# Power.net
KiCad netlist of a schematic drawn in Altium Designer
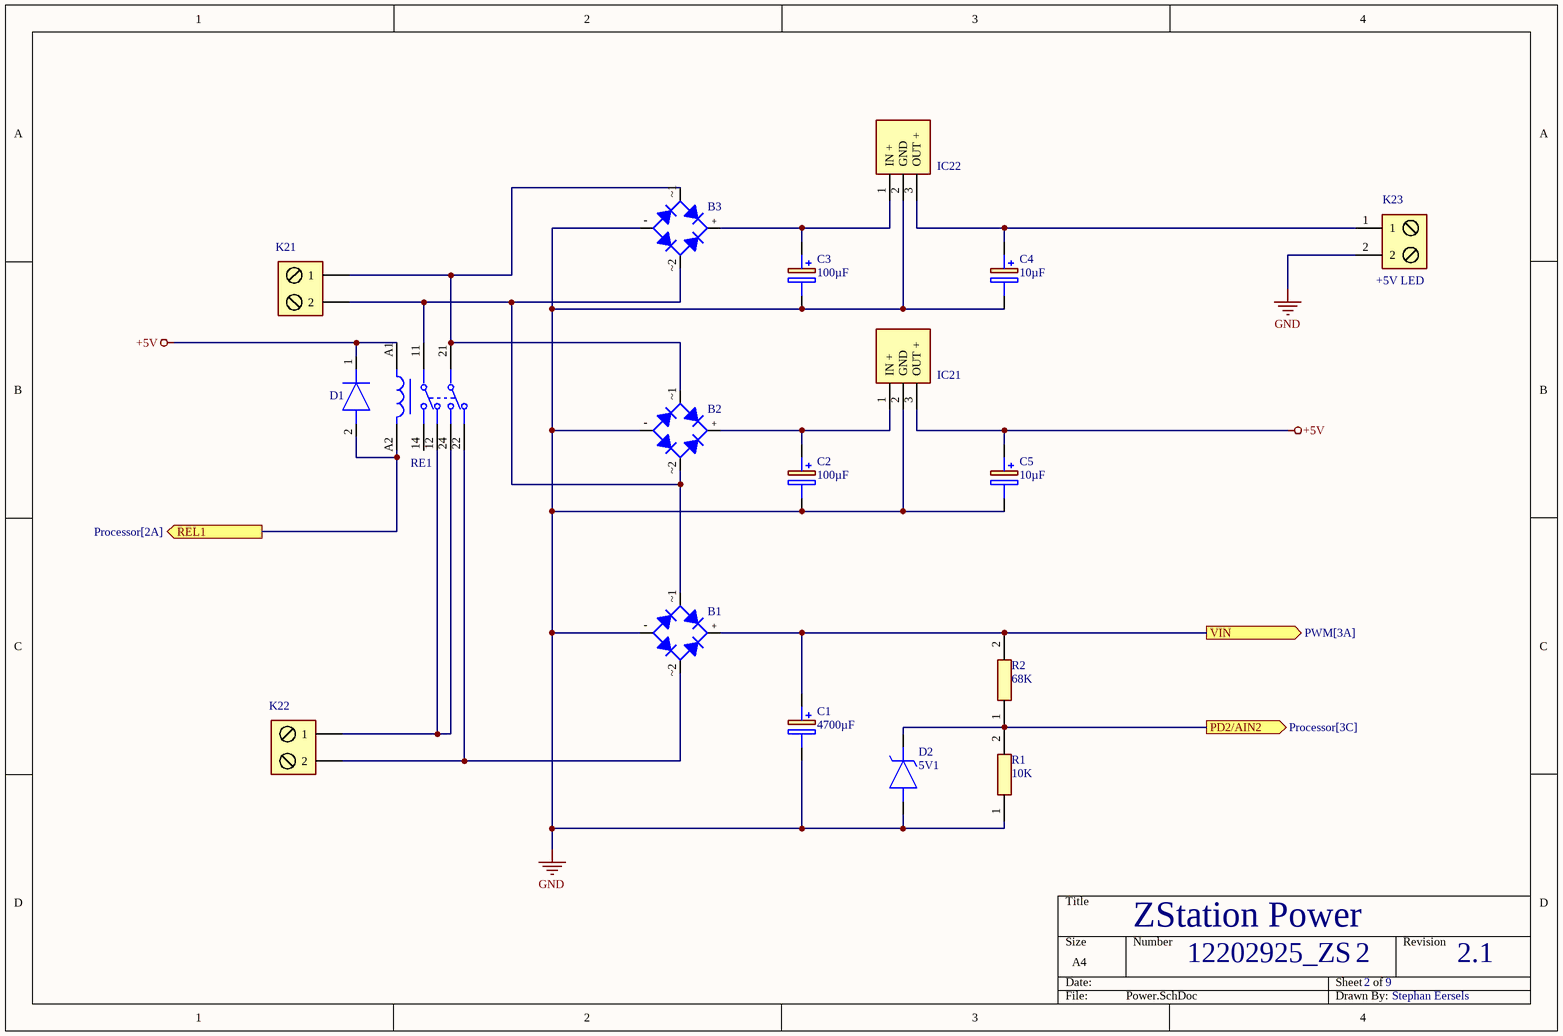
[diagram p0: Power.SchDoc]

(export (version "E")
  (design (tool "Eeschema 10.0.6"))
  (components
    (comp (ref "B1")
      (value "Bridge_Classic")
      (footprint "GBU6JE345")
      (description "Bridge Rectifiers 6.0 Amp 600 Volt")
      (fields (field (name "MANUFACTURER") "Diodes Inc"))
      (libsource (lib "Master") (part "Bridge_Classic"))
    )
    (comp (ref "B2")
      (value "Bridge_Classic")
      (footprint "GBU6JE345")
      (description "Bridge Rectifiers 6.0 Amp 600 Volt")
      (fields (field (name "MANUFACTURER") "Diodes Inc"))
      (libsource (lib "Master") (part "Bridge_Classic"))
    )
    (comp (ref "B3")
      (value "Bridge_Classic")
      (footprint "GBU6JE345")
      (description "Bridge Rectifiers 6.0 Amp 600 Volt")
      (fields (field (name "MANUFACTURER") "Diodes Inc"))
      (libsource (lib "Master") (part "Bridge_Classic"))
    )
    (comp (ref "C1")
      (value "4700µF")
      (footprint "SamacSys:CAPPRD250W52D630H1250")
      (description "Aluminium Electrolytic Capacitors - Radial Leaded WCAP-ATG8 4700uF 50V 20% Radial")
      (fields
        (field (name "MANUFACTURER_PART_NUMBER") "860040473003")
        (field (name "MOUSER PART NUMBER") "710-860040473003")
      )
      (libsource (lib "Master") (part "CAP_4700µF_50V"))
    )
    (comp (ref "C2")
      (value "100µF")
      (footprint "SamacSys:CAPPRD250W52D630H1250")
      (description "Aluminium Electrolytic Capacitors - Radial Leaded WCAP-ATUL 100uF 25V 20% Radial")
      (fields
        (field (name "MANUFACTURER_PART_NUMBER") "860040473003")
        (field (name "MOUSER PART NUMBER") "710-860040473003")
      )
      (libsource (lib "Master") (part "CAP_100µF_25V"))
    )
    (comp (ref "C3")
      (value "100µF")
      (footprint "SamacSys:CAPPRD250W52D630H1250")
      (description "Aluminium Electrolytic Capacitors - Radial Leaded WCAP-ATUL 100uF 25V 20% Radial")
      (fields
        (field (name "MANUFACTURER_PART_NUMBER") "860040473003")
        (field (name "MOUSER PART NUMBER") "710-860040473003")
      )
      (libsource (lib "Master") (part "CAP_100µF_25V"))
    )
    (comp (ref "C4")
      (value "10µF")
      (footprint "SamacSys:CAPPRD250W52D630H1250")
      (description "Aluminium Electrolytic Capacitors - Radial Leaded WCAP-AT1H 10uF 50V 20% Radial")
      (fields
        (field (name "MANUFACTURER_PART_NUMBER") "860040473003")
        (field (name "MOUSER PART NUMBER") "710-860040473003")
      )
      (libsource (lib "Master") (part "CAP_10µF_50V"))
    )
    (comp (ref "C5")
      (value "10µF")
      (footprint "SamacSys:CAPPRD250W52D630H1250")
      (description "Aluminium Electrolytic Capacitors - Radial Leaded WCAP-AT1H 10uF 50V 20% Radial")
      (fields
        (field (name "MANUFACTURER_PART_NUMBER") "860040473003")
        (field (name "MOUSER PART NUMBER") "710-860040473003")
      )
      (libsource (lib "Master") (part "CAP_10µF_50V"))
    )
    (comp (ref "D1")
      (value "~")
      (footprint "Master:1N4007")
      (description "Diode 1N4007")
      (fields
        (field (name "MANUFACTURER_PART_NUMBER") "1N4007")
        (field (name "MOUSER PART NUMBER") "637-1N4007")
      )
      (libsource (lib "Master") (part "1N4007"))
    )
    (comp (ref "D2")
      (value "5V1")
      (footprint "SamacSys:DIOAD950W60L350D150")
      (description "Zener Diode 5.1 Volt 0.5W 5%")
      (fields
        (field (name "MANUFACTURER_PART_NUMBER") "TZX5V1B-TR")
        (field (name "MOUSER PART NUMBER") "78-TZX5V1B")
      )
      (libsource (lib "Master") (part "ZEN_5V1_TH"))
    )
    (comp (ref "IC21")
      (value "OKI-78SR-5_1.5-W36-C")
      (footprint "SamacSys:OKI78SR515W36C")
      (description "Non-Isolated DC/DC Converter 7.5W 12VIN 5VOUT 1.5A DC/DC")
      (fields
        (field (name "MANUFACTURER_PART_NUMBER") "OKI-78SR-5/1.5-W36-C")
        (field (name "MOUSER PART NUMBER") "580-OKI78SR5/1.5W36C")
      )
      (libsource (lib "Master") (part "OKI-78SR-5_1.5-W36-C"))
    )
    (comp (ref "IC22")
      (value "OKI-78SR-5_1.5-W36-C")
      (footprint "SamacSys:OKI78SR515W36C")
      (description "Non-Isolated DC/DC Converter 7.5W 12VIN 5VOUT 1.5A DC/DC")
      (fields
        (field (name "MANUFACTURER_PART_NUMBER") "OKI-78SR-5/1.5-W36-C")
        (field (name "MOUSER PART NUMBER") "580-OKI78SR5/1.5W36C")
      )
      (libsource (lib "Master") (part "OKI-78SR-5_1.5-W36-C"))
    )
    (comp (ref "K21")
      (value "TBLOCK_2P")
      (footprint "TBLOCK_2P")
      (description "Connector")
      (fields
        (field (name "MANUFACTURER_PART_NUMBER") "691104700002")
        (field (name "MOUSER PART NUMBER") "710-691104700002")
      )
      (libsource (lib "Master") (part "TBLOCK_2P"))
    )
    (comp (ref "K22")
      (value "TBLOCK_2P")
      (footprint "TBLOCK_2P")
      (description "Connector")
      (fields
        (field (name "MANUFACTURER_PART_NUMBER") "691104700002")
        (field (name "MOUSER PART NUMBER") "710-691104700002")
      )
      (libsource (lib "Master") (part "TBLOCK_2P"))
    )
    (comp (ref "K23")
      (value "+5V LED")
      (footprint "TBLOCK_2P")
      (description "Connector")
      (fields
        (field (name "MANUFACTURER_PART_NUMBER") "691104700002")
        (field (name "MOUSER PART NUMBER") "710-691104700002")
      )
      (libsource (lib "") (part "TBLOCK_2P_1"))
    )
    (comp (ref "R1")
      (value "10K")
      (footprint "VISHAY_CMF_60")
      (description "Through Hole 1W 10/68 Kohms 1%")
      (fields
        (field (name "MANUFACTURER_PART_NUMBER") "CMF6010K000FKEB")
        (field (name "MOUSER PART NUMBER") "71-CMF6010K000FKEB")
      )
      (libsource (lib "Master") (part "RES_68K_10K"))
    )
    (comp (ref "R2")
      (value "68K")
      (footprint "VISHAY_CMF_60")
      (description "Through Hole 1W 10/68 Kohms 1%")
      (fields
        (field (name "MANUFACTURER_PART_NUMBER") "CMF6010K000FKEB")
        (field (name "MOUSER PART NUMBER") "71-CMF6010K000FKEB")
      )
      (libsource (lib "Master") (part "RES_68K_10K"))
    )
    (comp (ref "RE1")
      (value "RELAY_GENERAL_PURPOSE")
      (footprint "RT424005F")
      (fields
        (field (name "MANUFACTURER PART NUMBER") "RT424005")
        (field (name "OCTOPART") "https://octopart.com/5-1393243-9-te+connectivity-41835766")
        (field (name "MANUFACTURER") "TE Connectivity")
      )
      (libsource (lib "Master") (part "RELAY_GENERAL_PURPOSE"))
    )
  )
  (nets
    (net (code "1") (name "+5V") (class "Default")
      (node (ref "C5") (pin "1") (pinfunction "+_1") (pintype "passive"))
      (node (ref "D1") (pin "1") (pinfunction "K_1") (pintype "passive"))
      (node (ref "IC21") (pin "3") (pinfunction "OUT_+_3") (pintype "passive"))
      (node (ref "RE1") (pin "A1") (pinfunction "A1_A1") (pintype "passive"))
    )
    (net (code "2") (name "/PD2{slash}AIN2") (class "Default")
      (node (ref "D2") (pin "1") (pinfunction "K_1") (pintype "passive"))
      (node (ref "R1") (pin "2") (pinfunction "2_2") (pintype "passive"))
      (node (ref "R2") (pin "1") (pinfunction "1_1") (pintype "passive"))
    )
    (net (code "3") (name "/REL1") (class "Default")
      (node (ref "D1") (pin "2") (pinfunction "A_2") (pintype "passive"))
      (node (ref "RE1") (pin "A2") (pinfunction "A2_A2") (pintype "passive"))
    )
    (net (code "4") (name "/VIN") (class "Default")
      (node (ref "B1") (pin "+") (pinfunction "K_+") (pintype "passive"))
      (node (ref "C1") (pin "1") (pinfunction "+_1") (pintype "passive"))
      (node (ref "R2") (pin "2") (pinfunction "2_2") (pintype "passive"))
    )
    (net (code "5") (name "GND") (class "Default")
      (node (ref "B1") (pin "-") (pinfunction "A_-") (pintype "passive"))
      (node (ref "B2") (pin "-") (pinfunction "A_-") (pintype "passive"))
      (node (ref "B3") (pin "-") (pinfunction "A_-") (pintype "passive"))
      (node (ref "C1") (pin "2") (pinfunction "-_2") (pintype "passive"))
      (node (ref "C2") (pin "2") (pinfunction "-_2") (pintype "passive"))
      (node (ref "C3") (pin "2") (pinfunction "-_2") (pintype "passive"))
      (node (ref "C4") (pin "2") (pinfunction "-_2") (pintype "passive"))
      (node (ref "C5") (pin "2") (pinfunction "-_2") (pintype "passive"))
      (node (ref "D2") (pin "2") (pinfunction "A_2") (pintype "passive"))
      (node (ref "IC21") (pin "2") (pinfunction "GND_2") (pintype "passive"))
      (node (ref "IC22") (pin "2") (pinfunction "GND_2") (pintype "passive"))
      (node (ref "K23") (pin "2") (pinfunction "2_2") (pintype "passive"))
      (node (ref "R1") (pin "1") (pinfunction "1_1") (pintype "passive"))
    )
    (net (code "6") (name "Net-(B1-C-Pad~1)") (class "Default")
      (node (ref "B1") (pin "~1") (pinfunction "C_~1") (pintype "passive"))
      (node (ref "B2") (pin "~2") (pinfunction "C_~2") (pintype "passive"))
      (node (ref "B3") (pin "~2") (pinfunction "C_~2") (pintype "passive"))
      (node (ref "K21") (pin "2") (pinfunction "2_2") (pintype "passive"))
      (node (ref "RE1") (pin "11") (pinfunction "11_11") (pintype "passive"))
    )
    (net (code "7") (name "Net-(B1-C-Pad~2)") (class "Default")
      (node (ref "B1") (pin "~2") (pinfunction "C_~2") (pintype "passive"))
      (node (ref "K22") (pin "2") (pinfunction "2_2") (pintype "passive"))
      (node (ref "RE1") (pin "22") (pinfunction "22_22") (pintype "passive"))
    )
    (net (code "8") (name "Net-(B2-C-Pad~1)") (class "Default")
      (node (ref "B2") (pin "~1") (pinfunction "C_~1") (pintype "passive"))
      (node (ref "B3") (pin "~1") (pinfunction "C_~1") (pintype "passive"))
      (node (ref "K21") (pin "1") (pinfunction "1_1") (pintype "passive"))
      (node (ref "RE1") (pin "21") (pinfunction "21_21") (pintype "passive"))
    )
    (net (code "9") (name "Net-(B2-K)") (class "Default")
      (node (ref "B2") (pin "+") (pinfunction "K_+") (pintype "passive"))
      (node (ref "C2") (pin "1") (pinfunction "+_1") (pintype "passive"))
      (node (ref "IC21") (pin "1") (pinfunction "IN_+_1") (pintype "passive"))
    )
    (net (code "10") (name "Net-(B3-K)") (class "Default")
      (node (ref "B3") (pin "+") (pinfunction "K_+") (pintype "passive"))
      (node (ref "C3") (pin "1") (pinfunction "+_1") (pintype "passive"))
      (node (ref "IC22") (pin "1") (pinfunction "IN_+_1") (pintype "passive"))
    )
    (net (code "11") (name "Net-(C4-+)") (class "Default")
      (node (ref "C4") (pin "1") (pinfunction "+_1") (pintype "passive"))
      (node (ref "IC22") (pin "3") (pinfunction "OUT_+_3") (pintype "passive"))
      (node (ref "K23") (pin "1") (pinfunction "1_1") (pintype "passive"))
    )
    (net (code "12") (name "Net-(K22-Pad1)") (class "Default")
      (node (ref "K22") (pin "1") (pinfunction "1_1") (pintype "passive"))
      (node (ref "RE1") (pin "12") (pinfunction "12_12") (pintype "passive"))
      (node (ref "RE1") (pin "24") (pinfunction "24_24") (pintype "passive"))
    )
    (net (code "13") (name "unconnected-(RE1-Pad14)") (class "Default")
      (node (ref "RE1") (pin "14") (pinfunction "14_14") (pintype "passive"))
    )
  )
)
